# jtag-adapter-1-8.net
KiCad netlist of a schematic drawn in EAGLE
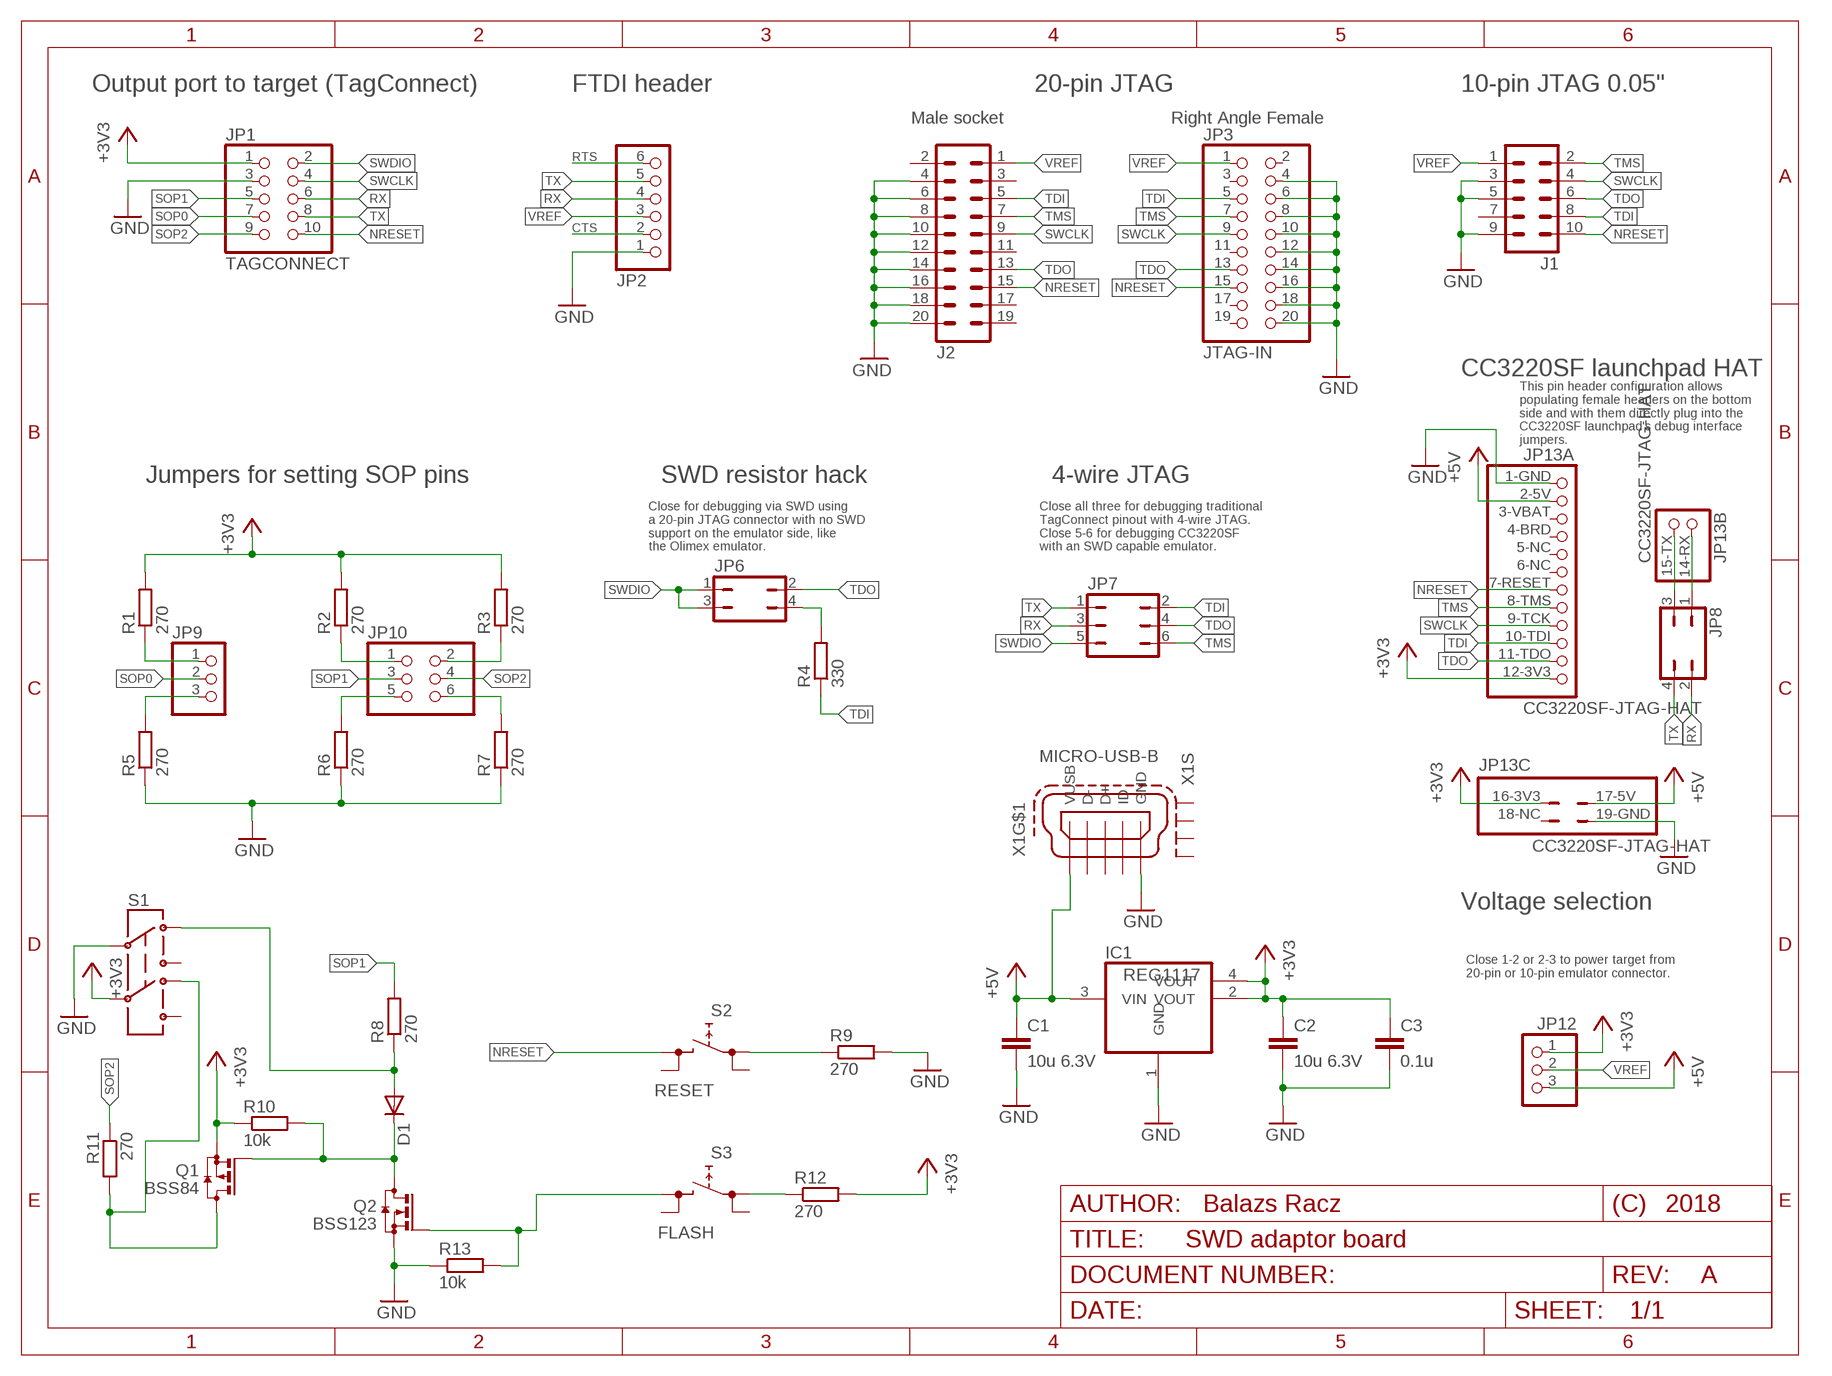
[diagram p0: schematic, sheet 1]

(export (version "E")
  (design (tool "Eeschema 10.0.6"))
  (components
    (comp (ref "C1")
      (value "10u 6.3V")
      (footprint "eagle-import:C0603K")
      (libsource (lib "eagle-import") (part "C-EUC0603K"))
    )
    (comp (ref "C2")
      (value "10u 6.3V")
      (footprint "eagle-import:C0603K")
      (libsource (lib "eagle-import") (part "C-EUC0603K"))
    )
    (comp (ref "C3")
      (value "0.1u")
      (footprint "eagle-import:C0603K")
      (libsource (lib "eagle-import") (part "C-EUC0603K"))
    )
    (comp (ref "D1")
      (value "DIODE-MINIMELF")
      (footprint "eagle-import:MINIMELF")
      (libsource (lib "eagle-import") (part "DIODE-MINIMELF"))
    )
    (comp (ref "IC1")
      (value "REG1117")
      (footprint "eagle-import:SOT223")
      (libsource (lib "eagle-import") (part "REG1117"))
    )
    (comp (ref "J1")
      (value "MA05-2_0.05X0.05")
      (footprint "eagle-import:MA05-2_0.05_X_0.05")
      (libsource (lib "eagle-import") (part "MA05-2_0.05X0.05"))
    )
    (comp (ref "J2")
      (value "MA10-2S")
      (footprint "eagle-import:MA10-2-SHROUDED")
      (libsource (lib "eagle-import") (part "MA10-2S"))
    )
    (comp (ref "JP1")
      (value "TAGCONNECT")
      (footprint "eagle-import:CON10M")
      (libsource (lib "eagle-import") (part "PINHD-2X5CN"))
    )
    (comp (ref "JP2")
      (value "PINHD-1X6")
      (footprint "eagle-import:1X06")
      (libsource (lib "eagle-import") (part "PINHD-1X6"))
    )
    (comp (ref "JP3")
      (value "JTAG-IN")
      (footprint "eagle-import:2X10")
      (libsource (lib "eagle-import") (part "PINHD-2X10"))
    )
    (comp (ref "JP6")
      (value "JP2Q")
      (footprint "eagle-import:JP2Q")
      (libsource (lib "eagle-import") (part "JP2Q"))
    )
    (comp (ref "JP7")
      (value "JP3Q")
      (footprint "eagle-import:JP3Q")
      (libsource (lib "eagle-import") (part "JP3Q"))
    )
    (comp (ref "JP8")
      (value "JP2Q")
      (footprint "eagle-import:JP2Q")
      (libsource (lib "eagle-import") (part "JP2Q"))
    )
    (comp (ref "JP9")
      (value "PINHD-1X3")
      (footprint "eagle-import:1X03")
      (libsource (lib "eagle-import") (part "PINHD-1X3"))
    )
    (comp (ref "JP10")
      (value "PINHD-2X3")
      (footprint "eagle-import:2X03")
      (libsource (lib "eagle-import") (part "PINHD-2X3"))
    )
    (comp (ref "JP12")
      (value "PINHD-1X3")
      (footprint "eagle-import:1X03")
      (libsource (lib "eagle-import") (part "PINHD-1X3"))
    )
    (comp (ref "JP13")
      (value "CC3220SF-JTAG-HAT")
      (footprint "eagle-import:JTAG-LAUNCHPAD-3220SF")
      (libsource (lib "eagle-import") (part "CC3220SF-JTAG-HAT"))
    )
    (comp (ref "Q1")
      (value "BSS84")
      (footprint "eagle-import:SOT23")
      (libsource (lib "eagle-import") (part "BSS84"))
    )
    (comp (ref "Q2")
      (value "BSS123")
      (footprint "eagle-import:SOT23")
      (libsource (lib "eagle-import") (part "BSS123"))
    )
    (comp (ref "R1")
      (value "270")
      (footprint "eagle-import:R0805")
      (libsource (lib "eagle-import") (part "R-EU_R0805"))
    )
    (comp (ref "R2")
      (value "270")
      (footprint "eagle-import:R0805")
      (libsource (lib "eagle-import") (part "R-EU_R0805"))
    )
    (comp (ref "R3")
      (value "270")
      (footprint "eagle-import:R0805")
      (libsource (lib "eagle-import") (part "R-EU_R0805"))
    )
    (comp (ref "R4")
      (value "330")
      (footprint "eagle-import:R0805")
      (libsource (lib "eagle-import") (part "R-EU_R0805"))
    )
    (comp (ref "R5")
      (value "270")
      (footprint "eagle-import:R0805")
      (libsource (lib "eagle-import") (part "R-EU_R0805"))
    )
    (comp (ref "R6")
      (value "270")
      (footprint "eagle-import:R0805")
      (libsource (lib "eagle-import") (part "R-EU_R0805"))
    )
    (comp (ref "R7")
      (value "270")
      (footprint "eagle-import:R0805")
      (libsource (lib "eagle-import") (part "R-EU_R0805"))
    )
    (comp (ref "R8")
      (value "270")
      (footprint "eagle-import:R0805")
      (libsource (lib "eagle-import") (part "R-EU_R0805"))
    )
    (comp (ref "R9")
      (value "270")
      (footprint "eagle-import:R0805")
      (libsource (lib "eagle-import") (part "R-EU_R0805"))
    )
    (comp (ref "R10")
      (value "10k")
      (footprint "eagle-import:R0805")
      (libsource (lib "eagle-import") (part "R-EU_R0805"))
    )
    (comp (ref "R11")
      (value "270")
      (footprint "eagle-import:R0805")
      (libsource (lib "eagle-import") (part "R-EU_R0805"))
    )
    (comp (ref "R12")
      (value "270")
      (footprint "eagle-import:R0805")
      (libsource (lib "eagle-import") (part "R-EU_R0805"))
    )
    (comp (ref "R13")
      (value "10k")
      (footprint "eagle-import:R0805")
      (libsource (lib "eagle-import") (part "R-EU_R0805"))
    )
    (comp (ref "S1")
      (value "SWITCH-DPDTJS202011CQN")
      (footprint "eagle-import:DPDT-2.5X3.2MM")
      (libsource (lib "eagle-import") (part "SWITCH-DPDTJS202011CQN"))
    )
    (comp (ref "S2")
      (value "RESET")
      (footprint "eagle-import:TACTSW-6X6")
      (libsource (lib "eagle-import") (part "TACTSW-6X6S"))
    )
    (comp (ref "S3")
      (value "FLASH")
      (footprint "eagle-import:TACTSW-6X6")
      (libsource (lib "eagle-import") (part "TACTSW-6X6S"))
    )
    (comp (ref "X1")
      (value "MICRO-USB-B")
      (footprint "eagle-import:MICRO-B-PAC")
      (libsource (lib "eagle-import") (part "MICRO-USB-B"))
    )
  )
  (nets
    (net (code "1") (name "+3V3") (class "Default")
      (node (ref "C2") (pin "1") (pinfunction "1_1") (pintype "passive"))
      (node (ref "C3") (pin "1") (pinfunction "1_1") (pintype "passive"))
      (node (ref "IC1") (pin "2") (pinfunction "VOUT_2") (pintype "output"))
      (node (ref "IC1") (pin "4") (pinfunction "VOUT_4") (pintype "output"))
      (node (ref "JP1") (pin "1") (pinfunction "1_1") (pintype "passive"))
      (node (ref "JP12") (pin "1") (pinfunction "1_1") (pintype "passive"))
      (node (ref "JP13") (pin "12-3V3") (pinfunction "12_12-3V3") (pintype "passive"))
      (node (ref "JP13") (pin "16-3V3") (pinfunction "1_16-3V3") (pintype "passive"))
      (node (ref "Q1") (pin "2") (pinfunction "S_2") (pintype "passive"))
      (node (ref "R1") (pin "2") (pinfunction "2_2") (pintype "passive"))
      (node (ref "R10") (pin "1") (pinfunction "1_1") (pintype "passive"))
      (node (ref "R12") (pin "2") (pinfunction "2_2") (pintype "passive"))
      (node (ref "R2") (pin "2") (pinfunction "2_2") (pintype "passive"))
      (node (ref "R3") (pin "2") (pinfunction "2_2") (pintype "passive"))
      (node (ref "S1") (pin "5") (pinfunction "2C_5") (pintype "bidirectional"))
    )
    (net (code "2") (name "+5V") (class "Default")
      (node (ref "C1") (pin "1") (pinfunction "1_1") (pintype "passive"))
      (node (ref "IC1") (pin "3") (pinfunction "VIN_3") (pintype "input"))
      (node (ref "JP12") (pin "3") (pinfunction "3_3") (pintype "passive"))
      (node (ref "JP13") (pin "17-5V") (pinfunction "2_17-5V") (pintype "passive"))
      (node (ref "JP13") (pin "2-5V") (pinfunction "2_2-5V") (pintype "passive"))
      (node (ref "X1") (pin "1") (pinfunction "VUSB_1") (pintype "passive"))
    )
    (net (code "3") (name "/CTS") (class "Default")
      (node (ref "JP2") (pin "2") (pinfunction "2_2") (pintype "passive"))
    )
    (net (code "4") (name "/RTS") (class "Default")
      (node (ref "JP2") (pin "6") (pinfunction "6_6") (pintype "passive"))
    )
    (net (code "5") (name "GND") (class "Default")
      (node (ref "C1") (pin "2") (pinfunction "2_2") (pintype "passive"))
      (node (ref "C2") (pin "2") (pinfunction "2_2") (pintype "passive"))
      (node (ref "C3") (pin "2") (pinfunction "2_2") (pintype "passive"))
      (node (ref "IC1") (pin "1") (pinfunction "GND_1") (pintype "power_in"))
      (node (ref "J1") (pin "3") (pinfunction "3_3") (pintype "passive"))
      (node (ref "J1") (pin "5") (pinfunction "5_5") (pintype "passive"))
      (node (ref "J1") (pin "9") (pinfunction "9_9") (pintype "passive"))
      (node (ref "J2") (pin "10") (pinfunction "10_10") (pintype "passive"))
      (node (ref "J2") (pin "12") (pinfunction "12_12") (pintype "passive"))
      (node (ref "J2") (pin "14") (pinfunction "14_14") (pintype "passive"))
      (node (ref "J2") (pin "16") (pinfunction "16_16") (pintype "passive"))
      (node (ref "J2") (pin "18") (pinfunction "18_18") (pintype "passive"))
      (node (ref "J2") (pin "20") (pinfunction "20_20") (pintype "passive"))
      (node (ref "J2") (pin "4") (pinfunction "4_4") (pintype "passive"))
      (node (ref "J2") (pin "6") (pinfunction "6_6") (pintype "passive"))
      (node (ref "J2") (pin "8") (pinfunction "8_8") (pintype "passive"))
      (node (ref "JP1") (pin "3") (pinfunction "3_3") (pintype "passive"))
      (node (ref "JP13") (pin "1-GND") (pinfunction "1_1-GND") (pintype "passive"))
      (node (ref "JP13") (pin "19-GND") (pinfunction "4_19-GND") (pintype "passive"))
      (node (ref "JP2") (pin "1") (pinfunction "1_1") (pintype "passive"))
      (node (ref "JP3") (pin "10") (pinfunction "10_10") (pintype "passive"))
      (node (ref "JP3") (pin "12") (pinfunction "12_12") (pintype "passive"))
      (node (ref "JP3") (pin "14") (pinfunction "14_14") (pintype "passive"))
      (node (ref "JP3") (pin "16") (pinfunction "16_16") (pintype "passive"))
      (node (ref "JP3") (pin "18") (pinfunction "18_18") (pintype "passive"))
      (node (ref "JP3") (pin "20") (pinfunction "20_20") (pintype "passive"))
      (node (ref "JP3") (pin "4") (pinfunction "4_4") (pintype "passive"))
      (node (ref "JP3") (pin "6") (pinfunction "6_6") (pintype "passive"))
      (node (ref "JP3") (pin "8") (pinfunction "8_8") (pintype "passive"))
      (node (ref "Q2") (pin "2") (pinfunction "S_2") (pintype "passive"))
      (node (ref "R13") (pin "1") (pinfunction "1_1") (pintype "passive"))
      (node (ref "R5") (pin "1") (pinfunction "1_1") (pintype "passive"))
      (node (ref "R6") (pin "1") (pinfunction "1_1") (pintype "passive"))
      (node (ref "R7") (pin "1") (pinfunction "1_1") (pintype "passive"))
      (node (ref "R9") (pin "2") (pinfunction "2_2") (pintype "passive"))
      (node (ref "S1") (pin "2") (pinfunction "1C_2") (pintype "bidirectional"))
      (node (ref "X1") (pin "5") (pinfunction "GND_5") (pintype "passive"))
    )
    (net (code "6") (name "NRESET") (class "Default")
      (node (ref "J1") (pin "10") (pinfunction "10_10") (pintype "passive"))
      (node (ref "J2") (pin "15") (pinfunction "15_15") (pintype "passive"))
      (node (ref "JP1") (pin "10") (pinfunction "10_10") (pintype "passive"))
      (node (ref "JP13") (pin "7-RESET") (pinfunction "7_7-RESET") (pintype "passive"))
      (node (ref "JP3") (pin "15") (pinfunction "15_15") (pintype "passive"))
      (node (ref "S2") (pin "3") (pinfunction "2.1_3") (pintype "passive"))
    )
    (net (code "7") (name "Net-(JP6-Pad4)") (class "Default")
      (node (ref "JP6") (pin "4") (pinfunction "4_4") (pintype "passive"))
      (node (ref "R4") (pin "2") (pinfunction "2_2") (pintype "passive"))
    )
    (net (code "8") (name "Net-(JP9-Pad1)") (class "Default")
      (node (ref "JP9") (pin "1") (pinfunction "1_1") (pintype "passive"))
      (node (ref "R1") (pin "1") (pinfunction "1_1") (pintype "passive"))
    )
    (net (code "9") (name "Net-(JP9-Pad3)") (class "Default")
      (node (ref "JP9") (pin "3") (pinfunction "3_3") (pintype "passive"))
      (node (ref "R5") (pin "2") (pinfunction "2_2") (pintype "passive"))
    )
    (net (code "10") (name "Net-(JP10-Pad1)") (class "Default")
      (node (ref "JP10") (pin "1") (pinfunction "1_1") (pintype "passive"))
      (node (ref "R2") (pin "1") (pinfunction "1_1") (pintype "passive"))
    )
    (net (code "11") (name "Net-(JP10-Pad2)") (class "Default")
      (node (ref "JP10") (pin "2") (pinfunction "2_2") (pintype "passive"))
      (node (ref "R3") (pin "1") (pinfunction "1_1") (pintype "passive"))
    )
    (net (code "12") (name "Net-(JP10-Pad5)") (class "Default")
      (node (ref "JP10") (pin "5") (pinfunction "5_5") (pintype "passive"))
      (node (ref "R6") (pin "2") (pinfunction "2_2") (pintype "passive"))
    )
    (net (code "13") (name "Net-(JP10-Pad6)") (class "Default")
      (node (ref "JP10") (pin "6") (pinfunction "6_6") (pintype "passive"))
      (node (ref "R7") (pin "2") (pinfunction "2_2") (pintype "passive"))
    )
    (net (code "14") (name "Net-(JP13B-1)") (class "Default")
      (node (ref "JP13") (pin "14-RX") (pinfunction "1_14-RX") (pintype "passive"))
      (node (ref "JP8") (pin "1") (pinfunction "1_1") (pintype "passive"))
    )
    (net (code "15") (name "Net-(JP13B-2)") (class "Default")
      (node (ref "JP13") (pin "15-TX") (pinfunction "2_15-TX") (pintype "passive"))
      (node (ref "JP8") (pin "3") (pinfunction "3_3") (pintype "passive"))
    )
    (net (code "16") (name "Net-(Q1-D)") (class "Default")
      (node (ref "Q1") (pin "3") (pinfunction "D_3") (pintype "passive"))
      (node (ref "R11") (pin "2") (pinfunction "2_2") (pintype "passive"))
      (node (ref "S1") (pin "4") (pinfunction "2A_4") (pintype "bidirectional"))
    )
    (net (code "17") (name "Net-(Q1-G)") (class "Default")
      (node (ref "D1") (pin "C") (pinfunction "C_C") (pintype "passive"))
      (node (ref "Q1") (pin "1") (pinfunction "G_1") (pintype "passive"))
      (node (ref "Q2") (pin "3") (pinfunction "D_3") (pintype "passive"))
      (node (ref "R10") (pin "2") (pinfunction "2_2") (pintype "passive"))
    )
    (net (code "18") (name "Net-(Q2-G)") (class "Default")
      (node (ref "Q2") (pin "1") (pinfunction "G_1") (pintype "passive"))
      (node (ref "R13") (pin "2") (pinfunction "2_2") (pintype "passive"))
      (node (ref "S3") (pin "3") (pinfunction "2.1_3") (pintype "passive"))
    )
    (net (code "19") (name "Net-(S1-1A)") (class "Default")
      (node (ref "D1") (pin "A") (pinfunction "A_A") (pintype "passive"))
      (node (ref "R8") (pin "1") (pinfunction "1_1") (pintype "passive"))
      (node (ref "S1") (pin "1") (pinfunction "1A_1") (pintype "bidirectional"))
    )
    (net (code "20") (name "Net-(S2-1.1)") (class "Default")
      (node (ref "R9") (pin "1") (pinfunction "1_1") (pintype "passive"))
      (node (ref "S2") (pin "1") (pinfunction "1.1_1") (pintype "passive"))
    )
    (net (code "21") (name "Net-(S3-1.1)") (class "Default")
      (node (ref "R12") (pin "1") (pinfunction "1_1") (pintype "passive"))
      (node (ref "S3") (pin "1") (pinfunction "1.1_1") (pintype "passive"))
    )
    (net (code "22") (name "RX") (class "Default")
      (node (ref "JP1") (pin "6") (pinfunction "6_6") (pintype "passive"))
      (node (ref "JP2") (pin "4") (pinfunction "4_4") (pintype "passive"))
      (node (ref "JP7") (pin "3") (pinfunction "3_3") (pintype "passive"))
      (node (ref "JP8") (pin "2") (pinfunction "2_2") (pintype "passive"))
    )
    (net (code "23") (name "SOP0") (class "Default")
      (node (ref "JP1") (pin "7") (pinfunction "7_7") (pintype "passive"))
      (node (ref "JP9") (pin "2") (pinfunction "2_2") (pintype "passive"))
    )
    (net (code "24") (name "SOP1") (class "Default")
      (node (ref "JP1") (pin "5") (pinfunction "5_5") (pintype "passive"))
      (node (ref "JP10") (pin "3") (pinfunction "3_3") (pintype "passive"))
      (node (ref "R8") (pin "2") (pinfunction "2_2") (pintype "passive"))
    )
    (net (code "25") (name "SOP2") (class "Default")
      (node (ref "JP1") (pin "9") (pinfunction "9_9") (pintype "passive"))
      (node (ref "JP10") (pin "4") (pinfunction "4_4") (pintype "passive"))
      (node (ref "R11") (pin "1") (pinfunction "1_1") (pintype "passive"))
    )
    (net (code "26") (name "SWCLK") (class "Default")
      (node (ref "J1") (pin "4") (pinfunction "4_4") (pintype "passive"))
      (node (ref "J2") (pin "9") (pinfunction "9_9") (pintype "passive"))
      (node (ref "JP1") (pin "4") (pinfunction "4_4") (pintype "passive"))
      (node (ref "JP13") (pin "9-TCK") (pinfunction "9_9-TCK") (pintype "passive"))
      (node (ref "JP3") (pin "9") (pinfunction "9_9") (pintype "passive"))
    )
    (net (code "27") (name "SWDIO") (class "Default")
      (node (ref "JP1") (pin "2") (pinfunction "2_2") (pintype "passive"))
      (node (ref "JP6") (pin "1") (pinfunction "1_1") (pintype "passive"))
      (node (ref "JP6") (pin "3") (pinfunction "3_3") (pintype "passive"))
      (node (ref "JP7") (pin "5") (pinfunction "5_5") (pintype "passive"))
    )
    (net (code "28") (name "TDI") (class "Default")
      (node (ref "J1") (pin "8") (pinfunction "8_8") (pintype "passive"))
      (node (ref "J2") (pin "5") (pinfunction "5_5") (pintype "passive"))
      (node (ref "JP13") (pin "10-TDI") (pinfunction "10_10-TDI") (pintype "passive"))
      (node (ref "JP3") (pin "5") (pinfunction "5_5") (pintype "passive"))
      (node (ref "JP7") (pin "2") (pinfunction "2_2") (pintype "passive"))
      (node (ref "R4") (pin "1") (pinfunction "1_1") (pintype "passive"))
    )
    (net (code "29") (name "TDO") (class "Default")
      (node (ref "J1") (pin "6") (pinfunction "6_6") (pintype "passive"))
      (node (ref "J2") (pin "13") (pinfunction "13_13") (pintype "passive"))
      (node (ref "JP13") (pin "11-TDO") (pinfunction "11_11-TDO") (pintype "passive"))
      (node (ref "JP3") (pin "13") (pinfunction "13_13") (pintype "passive"))
      (node (ref "JP6") (pin "2") (pinfunction "2_2") (pintype "passive"))
      (node (ref "JP7") (pin "4") (pinfunction "4_4") (pintype "passive"))
    )
    (net (code "30") (name "TMS") (class "Default")
      (node (ref "J1") (pin "2") (pinfunction "2_2") (pintype "passive"))
      (node (ref "J2") (pin "7") (pinfunction "7_7") (pintype "passive"))
      (node (ref "JP13") (pin "8-TMS") (pinfunction "8_8-TMS") (pintype "passive"))
      (node (ref "JP3") (pin "7") (pinfunction "7_7") (pintype "passive"))
      (node (ref "JP7") (pin "6") (pinfunction "6_6") (pintype "passive"))
    )
    (net (code "31") (name "TX") (class "Default")
      (node (ref "JP1") (pin "8") (pinfunction "8_8") (pintype "passive"))
      (node (ref "JP2") (pin "5") (pinfunction "5_5") (pintype "passive"))
      (node (ref "JP7") (pin "1") (pinfunction "1_1") (pintype "passive"))
      (node (ref "JP8") (pin "4") (pinfunction "4_4") (pintype "passive"))
    )
    (net (code "32") (name "VREF") (class "Default")
      (node (ref "J1") (pin "1") (pinfunction "1_1") (pintype "passive"))
      (node (ref "J2") (pin "1") (pinfunction "1_1") (pintype "passive"))
      (node (ref "JP12") (pin "2") (pinfunction "2_2") (pintype "passive"))
      (node (ref "JP2") (pin "3") (pinfunction "3_3") (pintype "passive"))
      (node (ref "JP3") (pin "1") (pinfunction "1_1") (pintype "passive"))
    )
    (net (code "33") (name "unconnected-(J1-Pad7)") (class "Default")
      (node (ref "J1") (pin "7") (pinfunction "7_7") (pintype "passive"))
    )
    (net (code "34") (name "unconnected-(J2-Pad2)") (class "Default")
      (node (ref "J2") (pin "2") (pinfunction "2_2") (pintype "passive"))
    )
    (net (code "35") (name "unconnected-(J2-Pad3)") (class "Default")
      (node (ref "J2") (pin "3") (pinfunction "3_3") (pintype "passive"))
    )
    (net (code "36") (name "unconnected-(J2-Pad11)") (class "Default")
      (node (ref "J2") (pin "11") (pinfunction "11_11") (pintype "passive"))
    )
    (net (code "37") (name "unconnected-(J2-Pad17)") (class "Default")
      (node (ref "J2") (pin "17") (pinfunction "17_17") (pintype "passive"))
    )
    (net (code "38") (name "unconnected-(J2-Pad19)") (class "Default")
      (node (ref "J2") (pin "19") (pinfunction "19_19") (pintype "passive"))
    )
    (net (code "39") (name "unconnected-(JP3-Pad2)") (class "Default")
      (node (ref "JP3") (pin "2") (pinfunction "2_2") (pintype "passive"))
    )
    (net (code "40") (name "unconnected-(JP3-Pad3)") (class "Default")
      (node (ref "JP3") (pin "3") (pinfunction "3_3") (pintype "passive"))
    )
    (net (code "41") (name "unconnected-(JP3-Pad11)") (class "Default")
      (node (ref "JP3") (pin "11") (pinfunction "11_11") (pintype "passive"))
    )
    (net (code "42") (name "unconnected-(JP3-Pad17)") (class "Default")
      (node (ref "JP3") (pin "17") (pinfunction "17_17") (pintype "passive"))
    )
    (net (code "43") (name "unconnected-(JP3-Pad19)") (class "Default")
      (node (ref "JP3") (pin "19") (pinfunction "19_19") (pintype "passive"))
    )
    (net (code "44") (name "unconnected-(JP13A-3-Pad3-VBAT)") (class "Default")
      (node (ref "JP13") (pin "3-VBAT") (pinfunction "3_3-VBAT") (pintype "passive"))
    )
    (net (code "45") (name "unconnected-(JP13A-4-Pad4-BRD)") (class "Default")
      (node (ref "JP13") (pin "4-BRD") (pinfunction "4_4-BRD") (pintype "passive"))
    )
    (net (code "46") (name "unconnected-(JP13A-5-Pad5-NC)") (class "Default")
      (node (ref "JP13") (pin "5-NC") (pinfunction "5_5-NC") (pintype "passive"))
    )
    (net (code "47") (name "unconnected-(JP13A-6-Pad6-NC)") (class "Default")
      (node (ref "JP13") (pin "6-NC") (pinfunction "6_6-NC") (pintype "passive"))
    )
    (net (code "48") (name "unconnected-(JP13C-3-Pad18-NC)") (class "Default")
      (node (ref "JP13") (pin "18-NC") (pinfunction "3_18-NC") (pintype "passive"))
    )
    (net (code "49") (name "unconnected-(S1-1B-Pad3)") (class "Default")
      (node (ref "S1") (pin "3") (pinfunction "1B_3") (pintype "bidirectional"))
    )
    (net (code "50") (name "unconnected-(S1-2B-Pad6)") (class "Default")
      (node (ref "S1") (pin "6") (pinfunction "2B_6") (pintype "bidirectional"))
    )
    (net (code "51") (name "unconnected-(S2-1.2-Pad2)") (class "Default")
      (node (ref "S2") (pin "2") (pinfunction "1.2_2") (pintype "passive"))
    )
    (net (code "52") (name "unconnected-(S2-2.2-Pad4)") (class "Default")
      (node (ref "S2") (pin "4") (pinfunction "2.2_4") (pintype "passive"))
    )
    (net (code "53") (name "unconnected-(S3-1.2-Pad2)") (class "Default")
      (node (ref "S3") (pin "2") (pinfunction "1.2_2") (pintype "passive"))
    )
    (net (code "54") (name "unconnected-(S3-2.2-Pad4)") (class "Default")
      (node (ref "S3") (pin "4") (pinfunction "2.2_4") (pintype "passive"))
    )
    (net (code "55") (name "unconnected-(X1A-D+-Pad3)") (class "Default")
      (node (ref "X1") (pin "3") (pinfunction "D+_3") (pintype "passive"))
    )
    (net (code "56") (name "unconnected-(X1A-D--Pad2)") (class "Default")
      (node (ref "X1") (pin "2") (pinfunction "D-_2") (pintype "passive"))
    )
    (net (code "57") (name "unconnected-(X1A-ID-Pad4)") (class "Default")
      (node (ref "X1") (pin "4") (pinfunction "ID_4") (pintype "passive"))
    )
    (net (code "58") (name "unconnected-(X1B-S1-PadM1)") (class "Default")
      (node (ref "X1") (pin "M1") (pinfunction "S1_M1") (pintype "passive"))
    )
    (net (code "59") (name "unconnected-(X1B-S2-PadM2)") (class "Default")
      (node (ref "X1") (pin "M2") (pinfunction "S2_M2") (pintype "passive"))
    )
    (net (code "60") (name "unconnected-(X1B-S3-PadM3)") (class "Default")
      (node (ref "X1") (pin "M3") (pinfunction "S3_M3") (pintype "passive"))
    )
    (net (code "61") (name "unconnected-(X1B-S4-PadM4)") (class "Default")
      (node (ref "X1") (pin "M4") (pinfunction "S4_M4") (pintype "passive"))
    )
  )
)
